# Power_Supply.net
KiCad netlist of a schematic drawn in Altium Designer
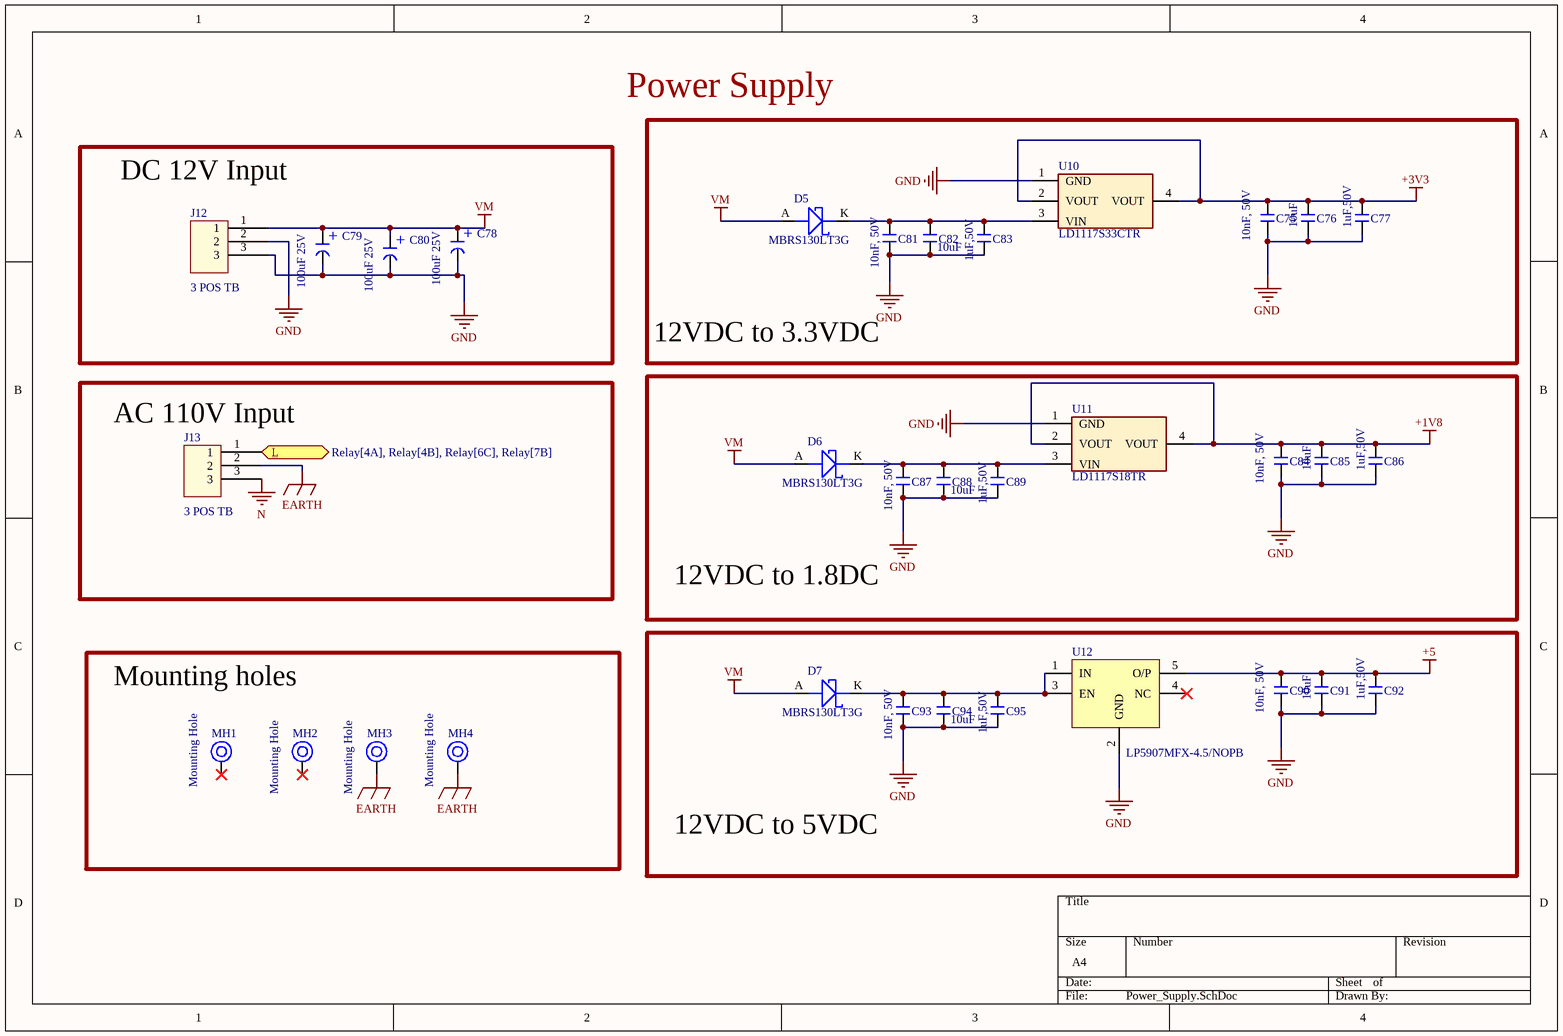
[diagram p0: Power_Supply.SchDoc]

(export (version "E")
  (design (tool "Eeschema 10.0.6"))
  (components
    (comp (ref "C75")
      (value "10nF, 50V")
      (footprint "Capacitor_0805")
      (description "Multilayer Ceramic Capacitors MLCC - SMD/SMT 50V 0.01uF X7R 0805 10% AEC-Q200")
      (fields
        (field (name "MANUFACTURER") "KEMET")
        (field (name "MANUFACTURER PART NUMBER") "C0805C103K5RECAUTO")
      )
      (libsource (lib "Schematics_Library_Hanif") (part "Cap_10nF_0805"))
    )
    (comp (ref "C76")
      (value "10uF")
      (footprint "Capacitor_1206_SMD")
      (description "Multilayer Ceramic Capacitor, 10 uF, 50 V, ï¿½ 10%, X7R, 1206 [3216 Metric]")
      (fields
        (field (name "MANUFACTURER") "Samsung")
        (field (name "MANUFACTURER PART NUMBER") "CL31B106KBHNNNE")
      )
      (libsource (lib "Schematics_Library_Hanif") (part "Cap_10uF_1206"))
    )
    (comp (ref "C77")
      (value "1uF,50V")
      (footprint "Capacitor_0805")
      (description "0805 1 uF 50 V ±5 % Tolerance X7R Surface Mount Multilayer Ceramic Capacitor")
      (fields
        (field (name "MANUFACTURER") "Yageo")
        (field (name "MANUFACTURER PART NUMBER") "CC0805JKX7R9BB105")
      )
      (libsource (lib "Schematics_Library_Hanif") (part "Cap_1uF_0805"))
    )
    (comp (ref "C78")
      (value "100uF 25V")
      (footprint "Capacitor_Radial_SMD_6.3mm_Dia")
      (description "Radial Can - SMD ALUMINUM ELECTROLYTIC CAPACITOR UWT 25V 100muF ±20% 0.248Dia 6.30mm")
      (fields
        (field (name "MANUFACTURER") "Nichicon")
        (field (name "MANUFACTURER PART NUMBER") "UWT1E101MCL1GS")
      )
      (libsource (lib "Schematics_Library_Hanif") (part "CAP_100uF_25V_Alum"))
    )
    (comp (ref "C79")
      (value "100uF 25V")
      (footprint "Capacitor_Radial_SMD_6.3mm_Dia")
      (description "Radial Can - SMD ALUMINUM ELECTROLYTIC CAPACITOR UWT 25V 100muF ±20% 0.248Dia 6.30mm")
      (fields
        (field (name "MANUFACTURER") "Nichicon")
        (field (name "MANUFACTURER PART NUMBER") "UWT1E101MCL1GS")
      )
      (libsource (lib "Schematics_Library_Hanif") (part "CAP_100uF_25V_Alum"))
    )
    (comp (ref "C80")
      (value "100uF 25V")
      (footprint "Capacitor_Radial_SMD_6.3mm_Dia")
      (description "Radial Can - SMD ALUMINUM ELECTROLYTIC CAPACITOR UWT 25V 100muF ±20% 0.248Dia 6.30mm")
      (fields
        (field (name "MANUFACTURER") "Nichicon")
        (field (name "MANUFACTURER PART NUMBER") "UWT1E101MCL1GS")
      )
      (libsource (lib "Schematics_Library_Hanif") (part "CAP_100uF_25V_Alum"))
    )
    (comp (ref "C81")
      (value "10nF, 50V")
      (footprint "Capacitor_0805")
      (description "Multilayer Ceramic Capacitors MLCC - SMD/SMT 50V 0.01uF X7R 0805 10% AEC-Q200")
      (fields
        (field (name "MANUFACTURER") "KEMET")
        (field (name "MANUFACTURER PART NUMBER") "C0805C103K5RECAUTO")
      )
      (libsource (lib "Schematics_Library_Hanif") (part "Cap_10nF_0805"))
    )
    (comp (ref "C82")
      (value "10uF")
      (footprint "Capacitor_1206_SMD")
      (description "Multilayer Ceramic Capacitor, 10 uF, 50 V, ï¿½ 10%, X7R, 1206 [3216 Metric]")
      (fields
        (field (name "MANUFACTURER") "Samsung")
        (field (name "MANUFACTURER PART NUMBER") "CL31B106KBHNNNE")
      )
      (libsource (lib "Schematics_Library_Hanif") (part "Cap_10uF_1206"))
    )
    (comp (ref "C83")
      (value "1uF,50V")
      (footprint "Capacitor_0805")
      (description "0805 1 uF 50 V ±5 % Tolerance X7R Surface Mount Multilayer Ceramic Capacitor")
      (fields
        (field (name "MANUFACTURER") "Yageo")
        (field (name "MANUFACTURER PART NUMBER") "CC0805JKX7R9BB105")
      )
      (libsource (lib "Schematics_Library_Hanif") (part "Cap_1uF_0805"))
    )
    (comp (ref "C84")
      (value "10nF, 50V")
      (footprint "Capacitor_0805")
      (description "Multilayer Ceramic Capacitors MLCC - SMD/SMT 50V 0.01uF X7R 0805 10% AEC-Q200")
      (fields
        (field (name "MANUFACTURER") "KEMET")
        (field (name "MANUFACTURER PART NUMBER") "C0805C103K5RECAUTO")
      )
      (libsource (lib "Schematics_Library_Hanif") (part "Cap_10nF_0805"))
    )
    (comp (ref "C85")
      (value "10uF")
      (footprint "Capacitor_1206_SMD")
      (description "Multilayer Ceramic Capacitor, 10 uF, 50 V, ï¿½ 10%, X7R, 1206 [3216 Metric]")
      (fields
        (field (name "MANUFACTURER") "Samsung")
        (field (name "MANUFACTURER PART NUMBER") "CL31B106KBHNNNE")
      )
      (libsource (lib "Schematics_Library_Hanif") (part "Cap_10uF_1206"))
    )
    (comp (ref "C86")
      (value "1uF,50V")
      (footprint "Capacitor_0805")
      (description "0805 1 uF 50 V ±5 % Tolerance X7R Surface Mount Multilayer Ceramic Capacitor")
      (fields
        (field (name "MANUFACTURER") "Yageo")
        (field (name "MANUFACTURER PART NUMBER") "CC0805JKX7R9BB105")
      )
      (libsource (lib "Schematics_Library_Hanif") (part "Cap_1uF_0805"))
    )
    (comp (ref "C87")
      (value "10nF, 50V")
      (footprint "Capacitor_0805")
      (description "Multilayer Ceramic Capacitors MLCC - SMD/SMT 50V 0.01uF X7R 0805 10% AEC-Q200")
      (fields
        (field (name "MANUFACTURER") "KEMET")
        (field (name "MANUFACTURER PART NUMBER") "C0805C103K5RECAUTO")
      )
      (libsource (lib "Schematics_Library_Hanif") (part "Cap_10nF_0805"))
    )
    (comp (ref "C88")
      (value "10uF")
      (footprint "Capacitor_1206_SMD")
      (description "Multilayer Ceramic Capacitor, 10 uF, 50 V, ï¿½ 10%, X7R, 1206 [3216 Metric]")
      (fields
        (field (name "MANUFACTURER") "Samsung")
        (field (name "MANUFACTURER PART NUMBER") "CL31B106KBHNNNE")
      )
      (libsource (lib "Schematics_Library_Hanif") (part "Cap_10uF_1206"))
    )
    (comp (ref "C89")
      (value "1uF,50V")
      (footprint "Capacitor_0805")
      (description "0805 1 uF 50 V ±5 % Tolerance X7R Surface Mount Multilayer Ceramic Capacitor")
      (fields
        (field (name "MANUFACTURER") "Yageo")
        (field (name "MANUFACTURER PART NUMBER") "CC0805JKX7R9BB105")
      )
      (libsource (lib "Schematics_Library_Hanif") (part "Cap_1uF_0805"))
    )
    (comp (ref "C90")
      (value "10nF, 50V")
      (footprint "Capacitor_0805")
      (description "Multilayer Ceramic Capacitors MLCC - SMD/SMT 50V 0.01uF X7R 0805 10% AEC-Q200")
      (fields
        (field (name "MANUFACTURER") "KEMET")
        (field (name "MANUFACTURER PART NUMBER") "C0805C103K5RECAUTO")
      )
      (libsource (lib "Schematics_Library_Hanif") (part "Cap_10nF_0805"))
    )
    (comp (ref "C91")
      (value "10uF")
      (footprint "Capacitor_1206_SMD")
      (description "Multilayer Ceramic Capacitor, 10 uF, 50 V, ï¿½ 10%, X7R, 1206 [3216 Metric]")
      (fields
        (field (name "MANUFACTURER") "Samsung")
        (field (name "MANUFACTURER PART NUMBER") "CL31B106KBHNNNE")
      )
      (libsource (lib "Schematics_Library_Hanif") (part "Cap_10uF_1206"))
    )
    (comp (ref "C92")
      (value "1uF,50V")
      (footprint "Capacitor_0805")
      (description "0805 1 uF 50 V ±5 % Tolerance X7R Surface Mount Multilayer Ceramic Capacitor")
      (fields
        (field (name "MANUFACTURER") "Yageo")
        (field (name "MANUFACTURER PART NUMBER") "CC0805JKX7R9BB105")
      )
      (libsource (lib "Schematics_Library_Hanif") (part "Cap_1uF_0805"))
    )
    (comp (ref "C93")
      (value "10nF, 50V")
      (footprint "Capacitor_0805")
      (description "Multilayer Ceramic Capacitors MLCC - SMD/SMT 50V 0.01uF X7R 0805 10% AEC-Q200")
      (fields
        (field (name "MANUFACTURER") "KEMET")
        (field (name "MANUFACTURER PART NUMBER") "C0805C103K5RECAUTO")
      )
      (libsource (lib "Schematics_Library_Hanif") (part "Cap_10nF_0805"))
    )
    (comp (ref "C94")
      (value "10uF")
      (footprint "Capacitor_1206_SMD")
      (description "Multilayer Ceramic Capacitor, 10 uF, 50 V, ï¿½ 10%, X7R, 1206 [3216 Metric]")
      (fields
        (field (name "MANUFACTURER") "Samsung")
        (field (name "MANUFACTURER PART NUMBER") "CL31B106KBHNNNE")
      )
      (libsource (lib "Schematics_Library_Hanif") (part "Cap_10uF_1206"))
    )
    (comp (ref "C95")
      (value "1uF,50V")
      (footprint "Capacitor_0805")
      (description "0805 1 uF 50 V ±5 % Tolerance X7R Surface Mount Multilayer Ceramic Capacitor")
      (fields
        (field (name "MANUFACTURER") "Yageo")
        (field (name "MANUFACTURER PART NUMBER") "CC0805JKX7R9BB105")
      )
      (libsource (lib "Schematics_Library_Hanif") (part "Cap_1uF_0805"))
    )
    (comp (ref "D5")
      (value "MBRS130LT3G")
      (footprint "DIO_SMB_DO-214AA")
      (description "Diode Schottky 30V 2A Surface Mount SMB")
      (fields (field (name "MANUFACTURER") "ON Semiconductor"))
      (libsource (lib "Schematics_Library_Hanif") (part "DIO-S_445mV-30V-2A-SMB"))
    )
    (comp (ref "D6")
      (value "MBRS130LT3G")
      (footprint "DIO_SMB_DO-214AA")
      (description "Diode Schottky 30V 2A Surface Mount SMB")
      (fields (field (name "MANUFACTURER") "ON Semiconductor"))
      (libsource (lib "Schematics_Library_Hanif") (part "DIO-S_445mV-30V-2A-SMB"))
    )
    (comp (ref "D7")
      (value "MBRS130LT3G")
      (footprint "DIO_SMB_DO-214AA")
      (description "Diode Schottky 30V 2A Surface Mount SMB")
      (fields (field (name "MANUFACTURER") "ON Semiconductor"))
      (libsource (lib "Schematics_Library_Hanif") (part "DIO-S_445mV-30V-2A-SMB"))
    )
    (comp (ref "J12")
      (value "3 POS TB")
      (footprint "CON3_P196_691101710003_TH_ST")
      (description "3 Pins, 1 Row 5mm Pitch, straight Connector, male")
      (fields
        (field (name "MANUFACTURER") "Wurth Electronics")
        (field (name "MANUFACTURER PART NUMBER") "691101710003")
      )
      (libsource (lib "Schematics_Library_Hanif") (part "CON-TB_3X1-196-ST-TH"))
    )
    (comp (ref "J13")
      (value "3 POS TB")
      (footprint "CON3_P196_691101710003_TH_ST")
      (description "3 Pins, 1 Row 5mm Pitch, straight Connector, male")
      (fields
        (field (name "MANUFACTURER") "Wurth Electronics")
        (field (name "MANUFACTURER PART NUMBER") "691101710003")
      )
      (libsource (lib "Schematics_Library_Hanif") (part "CON-TB_3X1-196-ST-TH"))
    )
    (comp (ref "MH1")
      (value "Mounting Hole")
      (footprint "MOUNTING")
      (fields (field (name "MANUFACTURER PART NUMBER") "NA"))
      (libsource (lib "Schematics_Library_Hanif") (part "MH_3.5H_6D"))
    )
    (comp (ref "MH2")
      (value "Mounting Hole")
      (footprint "MOUNTING")
      (fields (field (name "MANUFACTURER PART NUMBER") "NA"))
      (libsource (lib "Schematics_Library_Hanif") (part "MH_3.5H_6D"))
    )
    (comp (ref "MH3")
      (value "Mounting Hole")
      (footprint "MOUNTING")
      (fields (field (name "MANUFACTURER PART NUMBER") "NA"))
      (libsource (lib "Schematics_Library_Hanif") (part "MH_3.5H_6D"))
    )
    (comp (ref "MH4")
      (value "Mounting Hole")
      (footprint "MOUNTING")
      (fields (field (name "MANUFACTURER PART NUMBER") "NA"))
      (libsource (lib "Schematics_Library_Hanif") (part "MH_3.5H_6D"))
    )
    (comp (ref "U10")
      (value "LD1117S33CTR")
      (footprint "SOT-223")
      (description "Linear Voltage Regulator IC 1 Output 800mA SOT-223")
      (fields (field (name "MANUFACTURER") "STMicroelectronics"))
      (libsource (lib "Schematics_Library_Hanif") (part "REG_15V-3.3V-0.9A-12W-SOT223"))
    )
    (comp (ref "U11")
      (value "LD1117S18TR")
      (footprint "SOT-223")
      (description "LDO Voltage Regulators 1.8V 0.8A Positive")
      (fields (field (name "MANUFACTURER") "STMicroelectronics"))
      (libsource (lib "Schematics_Library_Hanif") (part "REG_15V-1.8V-0.8A-1.4W-SOT223"))
    )
    (comp (ref "U12")
      (value "LP5907MFX-4.5/NOPB")
      (footprint "SOT23-5")
      (description "Linear Voltage Regulator IC 1 Output 250mA SOT-23-5")
      (fields (field (name "MANUFACTURER") "STMicroelectronics"))
      (libsource (lib "Schematics_Library_Hanif") (part "REG_5.5V-4.5V-0.25A-0.8W-SOT-23-5"))
    )
  )
  (nets
    (net (code "1") (name "+1V8") (class "Default")
      (node (ref "C84") (pin "2") (pinfunction "2_2") (pintype "passive"))
      (node (ref "C85") (pin "2") (pinfunction "2_2") (pintype "passive"))
      (node (ref "C86") (pin "2") (pinfunction "2_2") (pintype "passive"))
      (node (ref "U11") (pin "2") (pinfunction "VOUT_2") (pintype "passive"))
      (node (ref "U11") (pin "4") (pinfunction "VOUT_4") (pintype "passive"))
    )
    (net (code "2") (name "+3V3") (class "Default")
      (node (ref "C75") (pin "2") (pinfunction "2_2") (pintype "passive"))
      (node (ref "C76") (pin "2") (pinfunction "2_2") (pintype "passive"))
      (node (ref "C77") (pin "2") (pinfunction "2_2") (pintype "passive"))
      (node (ref "U10") (pin "2") (pinfunction "VOUT_2") (pintype "passive"))
      (node (ref "U10") (pin "4") (pinfunction "VOUT_4") (pintype "passive"))
    )
    (net (code "3") (name "+5") (class "Default")
      (node (ref "C90") (pin "2") (pinfunction "2_2") (pintype "passive"))
      (node (ref "C91") (pin "2") (pinfunction "2_2") (pintype "passive"))
      (node (ref "C92") (pin "2") (pinfunction "2_2") (pintype "passive"))
      (node (ref "U12") (pin "5") (pinfunction "O/P_5") (pintype "passive"))
    )
    (net (code "4") (name "/L") (class "Default")
      (node (ref "J13") (pin "1") (pinfunction "1_1") (pintype "passive"))
    )
    (net (code "5") (name "EARTH") (class "Default")
      (node (ref "J13") (pin "2") (pinfunction "2_2") (pintype "passive"))
      (node (ref "MH3") (pin "1") (pinfunction "1_1") (pintype "passive"))
      (node (ref "MH4") (pin "1") (pinfunction "1_1") (pintype "passive"))
    )
    (net (code "6") (name "GND") (class "Default")
      (node (ref "C75") (pin "1") (pinfunction "1_1") (pintype "passive"))
      (node (ref "C76") (pin "1") (pinfunction "1_1") (pintype "passive"))
      (node (ref "C77") (pin "1") (pinfunction "1_1") (pintype "passive"))
      (node (ref "C78") (pin "2") (pinfunction "2_2") (pintype "passive"))
      (node (ref "C79") (pin "2") (pinfunction "2_2") (pintype "passive"))
      (node (ref "C80") (pin "2") (pinfunction "2_2") (pintype "passive"))
      (node (ref "C81") (pin "1") (pinfunction "1_1") (pintype "passive"))
      (node (ref "C82") (pin "1") (pinfunction "1_1") (pintype "passive"))
      (node (ref "C83") (pin "1") (pinfunction "1_1") (pintype "passive"))
      (node (ref "C84") (pin "1") (pinfunction "1_1") (pintype "passive"))
      (node (ref "C85") (pin "1") (pinfunction "1_1") (pintype "passive"))
      (node (ref "C86") (pin "1") (pinfunction "1_1") (pintype "passive"))
      (node (ref "C87") (pin "1") (pinfunction "1_1") (pintype "passive"))
      (node (ref "C88") (pin "1") (pinfunction "1_1") (pintype "passive"))
      (node (ref "C89") (pin "1") (pinfunction "1_1") (pintype "passive"))
      (node (ref "C90") (pin "1") (pinfunction "1_1") (pintype "passive"))
      (node (ref "C91") (pin "1") (pinfunction "1_1") (pintype "passive"))
      (node (ref "C92") (pin "1") (pinfunction "1_1") (pintype "passive"))
      (node (ref "C93") (pin "1") (pinfunction "1_1") (pintype "passive"))
      (node (ref "C94") (pin "1") (pinfunction "1_1") (pintype "passive"))
      (node (ref "C95") (pin "1") (pinfunction "1_1") (pintype "passive"))
      (node (ref "J12") (pin "2") (pinfunction "2_2") (pintype "passive"))
      (node (ref "J12") (pin "3") (pinfunction "3_3") (pintype "passive"))
      (node (ref "U10") (pin "1") (pinfunction "GND_1") (pintype "passive"))
      (node (ref "U11") (pin "1") (pinfunction "GND_1") (pintype "passive"))
      (node (ref "U12") (pin "2") (pinfunction "GND_2") (pintype "passive"))
    )
    (net (code "7") (name "N") (class "Default")
      (node (ref "J13") (pin "3") (pinfunction "3_3") (pintype "passive"))
    )
    (net (code "8") (name "Net-(U10-VIN)") (class "Default")
      (node (ref "C81") (pin "2") (pinfunction "2_2") (pintype "passive"))
      (node (ref "C82") (pin "2") (pinfunction "2_2") (pintype "passive"))
      (node (ref "C83") (pin "2") (pinfunction "2_2") (pintype "passive"))
      (node (ref "D5") (pin "K") (pinfunction "K_K") (pintype "passive"))
      (node (ref "U10") (pin "3") (pinfunction "VIN_3") (pintype "passive"))
    )
    (net (code "9") (name "Net-(U11-VIN)") (class "Default")
      (node (ref "C87") (pin "2") (pinfunction "2_2") (pintype "passive"))
      (node (ref "C88") (pin "2") (pinfunction "2_2") (pintype "passive"))
      (node (ref "C89") (pin "2") (pinfunction "2_2") (pintype "passive"))
      (node (ref "D6") (pin "K") (pinfunction "K_K") (pintype "passive"))
      (node (ref "U11") (pin "3") (pinfunction "VIN_3") (pintype "passive"))
    )
    (net (code "10") (name "Net-(U12-EN)") (class "Default")
      (node (ref "C93") (pin "2") (pinfunction "2_2") (pintype "passive"))
      (node (ref "C94") (pin "2") (pinfunction "2_2") (pintype "passive"))
      (node (ref "C95") (pin "2") (pinfunction "2_2") (pintype "passive"))
      (node (ref "D7") (pin "K") (pinfunction "K_K") (pintype "passive"))
      (node (ref "U12") (pin "1") (pinfunction "IN_1") (pintype "passive"))
      (node (ref "U12") (pin "3") (pinfunction "EN_3") (pintype "passive"))
    )
    (net (code "11") (name "VM") (class "Default")
      (node (ref "C78") (pin "1") (pinfunction "1_1") (pintype "passive"))
      (node (ref "C79") (pin "1") (pinfunction "1_1") (pintype "passive"))
      (node (ref "C80") (pin "1") (pinfunction "1_1") (pintype "passive"))
      (node (ref "D5") (pin "A") (pinfunction "A_A") (pintype "passive"))
      (node (ref "D6") (pin "A") (pinfunction "A_A") (pintype "passive"))
      (node (ref "D7") (pin "A") (pinfunction "A_A") (pintype "passive"))
      (node (ref "J12") (pin "1") (pinfunction "1_1") (pintype "passive"))
    )
    (net (code "12") (name "unconnected-(MH1-Pad1)") (class "Default")
      (node (ref "MH1") (pin "1") (pinfunction "1_1") (pintype "passive+no_connect"))
    )
    (net (code "13") (name "unconnected-(MH2-Pad1)") (class "Default")
      (node (ref "MH2") (pin "1") (pinfunction "1_1") (pintype "passive+no_connect"))
    )
    (net (code "14") (name "unconnected-(U12-NC-Pad4)") (class "Default")
      (node (ref "U12") (pin "4") (pinfunction "NC_4") (pintype "passive+no_connect"))
    )
  )
)
